# design.net
KiCad netlist of a schematic drawn in Altium Designer
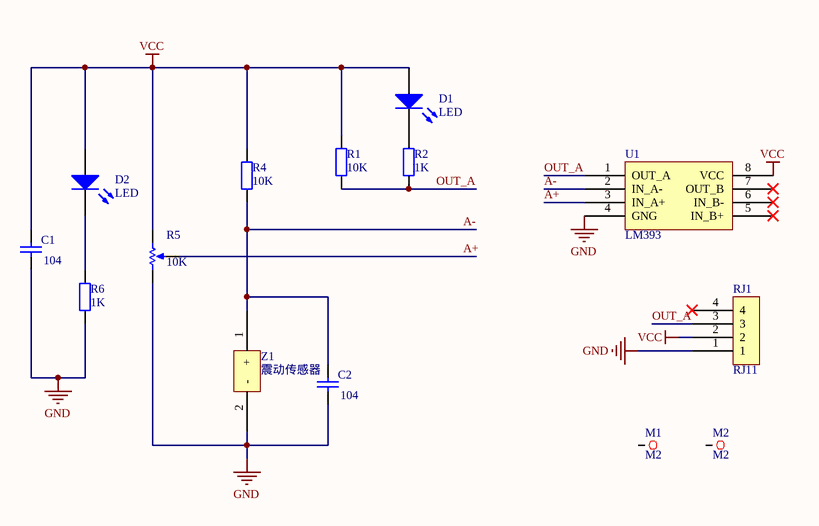
[diagram p0: 震动.SchDoc]

(export (version "E")
  (design (tool "Eeschema 10.0.6"))
  (components
    (comp (ref "C1")
      (value "104")
      (footprint "0603_C")
      (description "Capacitor")
      (fields (field (name "Comment") "Cap") (field (name "PUBLISHER") "Altium Limited"))
      (libsource (lib "Miscellaneous Devices") (part "Cap"))
    )
    (comp (ref "C2")
      (value "104")
      (footprint "0603_C")
      (description "Capacitor")
      (fields (field (name "Comment") "Cap") (field (name "PUBLISHER") "Altium Limited"))
      (libsource (lib "Miscellaneous Devices") (part "Cap"))
    )
    (comp (ref "D1")
      (value "LED")
      (footprint "0805")
      (description "Typical RED GaAs LED")
      (fields (field (name "PUBLISHER") "Altium Limited"))
      (libsource (lib "Miscellaneous Devices") (part "LED1"))
    )
    (comp (ref "D2")
      (value "LED")
      (footprint "0805")
      (description "Typical RED GaAs LED")
      (fields (field (name "PUBLISHER") "Altium Limited"))
      (libsource (lib "Miscellaneous Devices") (part "LED1"))
    )
    (comp (ref "M1") (value "M2") (footprint "M2") (libsource (lib "QQW-1.SCHLIB") (part "M3")))
    (comp (ref "M2") (value "M2") (footprint "M2") (libsource (lib "QQW-1.SCHLIB") (part "M3")))
    (comp (ref "R1")
      (value "10K")
      (footprint "0603_R")
      (description "Resistor")
      (fields (field (name "Comment") "Res2") (field (name "PUBLISHER") "Altium Limited"))
      (libsource (lib "Miscellaneous Devices") (part "Res2"))
    )
    (comp (ref "R2")
      (value "1K")
      (footprint "0603_R")
      (description "Resistor")
      (fields (field (name "Comment") "Res2") (field (name "PUBLISHER") "Altium Limited"))
      (libsource (lib "Miscellaneous Devices") (part "Res2"))
    )
    (comp (ref "R4")
      (value "10K")
      (footprint "0603_R")
      (description "Resistor")
      (fields (field (name "Comment") "Res2") (field (name "PUBLISHER") "Altium Limited"))
      (libsource (lib "Miscellaneous Devices") (part "Res2"))
    )
    (comp (ref "R5")
      (value "10K")
      (footprint "电位器")
      (description "Potentiometer")
      (fields (field (name "Comment") "RPot") (field (name "PUBLISHER") "Altium Limited"))
      (libsource (lib "Miscellaneous Devices") (part "RPot"))
    )
    (comp (ref "R6")
      (value "1K")
      (footprint "0603_R")
      (description "Resistor")
      (fields (field (name "Comment") "Res2") (field (name "PUBLISHER") "Altium Limited"))
      (libsource (lib "Miscellaneous Devices") (part "Res2"))
    )
    (comp (ref "RJ1") (value "RJ11") (footprint "RJ11") (libsource (lib "少儿智能车") (part "RJ11")))
    (comp (ref "U1") (value "LM393") (footprint "SO-8") (libsource (lib "Infrared") (part "LM393")))
    (comp (ref "Z1") (value "震动传感器") (footprint "震动传感器") (libsource (lib "震动") (part "震动传感器")))
  )
  (nets
    (net (code "1") (name "/A+") (class "Default")
      (node (ref "R5") (pin "3") (pinfunction "TAP_3") (pintype "passive"))
      (node (ref "U1") (pin "3") (pinfunction "IN_A+_3") (pintype "passive"))
    )
    (net (code "2") (name "/A-") (class "Default")
      (node (ref "C2") (pin "2") (pinfunction "2_2") (pintype "passive"))
      (node (ref "R4") (pin "1") (pinfunction "1_1") (pintype "passive"))
      (node (ref "U1") (pin "2") (pinfunction "IN_A-_2") (pintype "passive"))
      (node (ref "Z1") (pin "1") (pinfunction "+_1") (pintype "passive"))
    )
    (net (code "3") (name "/OUT_A") (class "Default")
      (node (ref "R1") (pin "1") (pinfunction "1_1") (pintype "passive"))
      (node (ref "R2") (pin "1") (pinfunction "1_1") (pintype "passive"))
      (node (ref "RJ1") (pin "3") (pinfunction "3_3") (pintype "passive"))
      (node (ref "U1") (pin "1") (pinfunction "OUT_A_1") (pintype "passive"))
    )
    (net (code "4") (name "GND") (class "Default")
      (node (ref "C1") (pin "1") (pinfunction "1_1") (pintype "passive"))
      (node (ref "C2") (pin "1") (pinfunction "1_1") (pintype "passive"))
      (node (ref "R5") (pin "1") (pinfunction "TOP_1") (pintype "passive"))
      (node (ref "R6") (pin "1") (pinfunction "1_1") (pintype "passive"))
      (node (ref "RJ1") (pin "1") (pinfunction "1_1") (pintype "passive"))
      (node (ref "U1") (pin "4") (pinfunction "GNG_4") (pintype "passive"))
      (node (ref "Z1") (pin "2") (pinfunction "-_2") (pintype "passive"))
    )
    (net (code "5") (name "Net-(D1-K)") (class "Default")
      (node (ref "D1") (pin "2") (pinfunction "K_2") (pintype "passive"))
      (node (ref "R2") (pin "2") (pinfunction "2_2") (pintype "passive"))
    )
    (net (code "6") (name "Net-(D2-K)") (class "Default")
      (node (ref "D2") (pin "2") (pinfunction "K_2") (pintype "passive"))
      (node (ref "R6") (pin "2") (pinfunction "2_2") (pintype "passive"))
    )
    (net (code "7") (name "VCC") (class "Default")
      (node (ref "C1") (pin "2") (pinfunction "2_2") (pintype "passive"))
      (node (ref "D1") (pin "1") (pinfunction "A_1") (pintype "passive"))
      (node (ref "D2") (pin "1") (pinfunction "A_1") (pintype "passive"))
      (node (ref "R1") (pin "2") (pinfunction "2_2") (pintype "passive"))
      (node (ref "R4") (pin "2") (pinfunction "2_2") (pintype "passive"))
      (node (ref "R5") (pin "2") (pinfunction "BOT_2") (pintype "passive"))
      (node (ref "RJ1") (pin "2") (pinfunction "2_2") (pintype "passive"))
      (node (ref "U1") (pin "8") (pinfunction "VCC_8") (pintype "passive"))
    )
    (net (code "8") (name "unconnected-(M1-Pad0)") (class "Default")
      (node (ref "M1") (pin "0") (pinfunction "0_0") (pintype "passive"))
    )
    (net (code "9") (name "unconnected-(M2-Pad0)") (class "Default")
      (node (ref "M2") (pin "0") (pinfunction "0_0") (pintype "passive"))
    )
    (net (code "10") (name "unconnected-(RJ1-Pad4)") (class "Default")
      (node (ref "RJ1") (pin "4") (pinfunction "4_4") (pintype "passive+no_connect"))
    )
    (net (code "11") (name "unconnected-(U1-IN_B+-Pad5)") (class "Default")
      (node (ref "U1") (pin "5") (pinfunction "IN_B+_5") (pintype "passive+no_connect"))
    )
    (net (code "12") (name "unconnected-(U1-IN_B--Pad6)") (class "Default")
      (node (ref "U1") (pin "6") (pinfunction "IN_B-_6") (pintype "passive+no_connect"))
    )
    (net (code "13") (name "unconnected-(U1-OUT_B-Pad7)") (class "Default")
      (node (ref "U1") (pin "7") (pinfunction "OUT_B_7") (pintype "passive+no_connect"))
    )
  )
)
